# Sheet6.net
KiCad netlist of a schematic drawn in Altium Designer
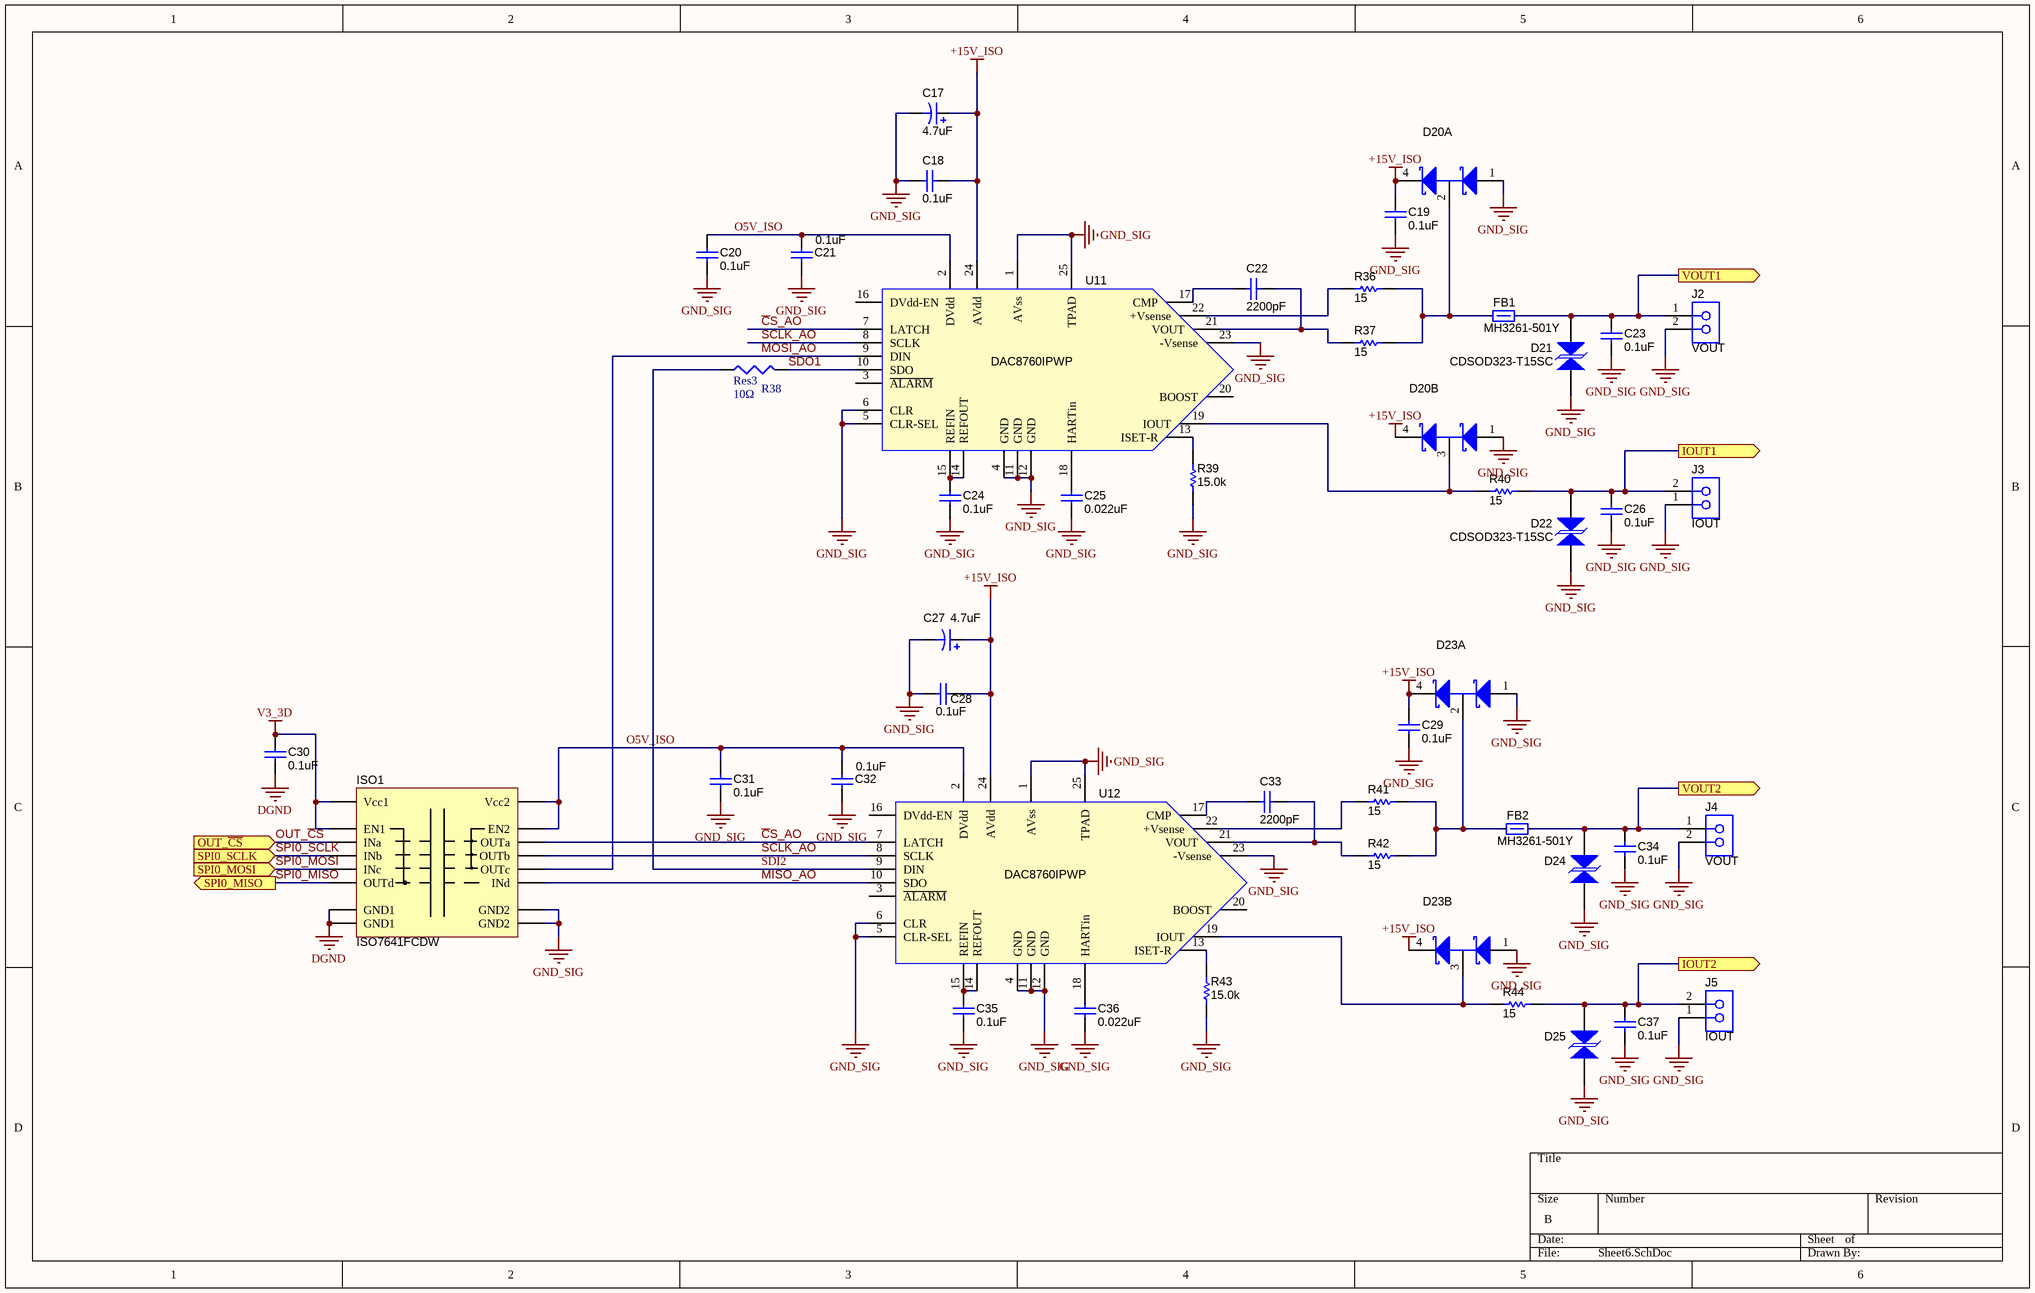
[diagram p0: Sheet6.SchDoc]

(export (version "E")
  (design (tool "Eeschema 10.0.6"))
  (components
    (comp (ref "C17")
      (value "293D475X9035C2TE3")
      (footprint "6032-28")
      (description "CAP, TA, 4.7uF, 35V, +/-10%, 1.9 ohm, SMD")
      (fields
        (field (name "VALUEDISPLAYED") "4.7uF")
        (field (name "MANUFACTURER") "Vishay-Sprague")
        (field (name "PUBLISHER") "Texas Instruments")
      )
      (libsource (lib "Capacitor_Tantalum") (part "293D475X9035C2TE3"))
    )
    (comp (ref "C18")
      (value "GRM188R71H104KA93D")
      (footprint "0805_cap")
      (description "CAP, CERM, 0.1uF, 50V, +/-10%, X7R, 0603")
      (fields
        (field (name "VALUEDISPLAYED") "0.1uF")
        (field (name "MANUFACTURER") "MuRata")
        (field (name "PUBLISHER") "Texas Instruments")
      )
      (libsource (lib "Capacitor_Ceramic") (part "GRM188R71H104KA93D"))
    )
    (comp (ref "C19")
      (value "GRM188R71H104KA93D")
      (footprint "0805_cap")
      (description "CAP, CERM, 0.1uF, 50V, +/-10%, X7R, 0603")
      (fields
        (field (name "VALUEDISPLAYED") "0.1uF")
        (field (name "MANUFACTURER") "MuRata")
        (field (name "PUBLISHER") "Texas Instruments")
      )
      (libsource (lib "Capacitor_Ceramic") (part "GRM188R71H104KA93D"))
    )
    (comp (ref "C20")
      (value "GRM188R71H104KA93D")
      (footprint "0805_cap")
      (description "CAP, CERM, 0.1uF, 50V, +/-10%, X7R, 0603")
      (fields
        (field (name "VALUEDISPLAYED") "0.1uF")
        (field (name "MANUFACTURER") "MuRata")
        (field (name "PUBLISHER") "Texas Instruments")
      )
      (libsource (lib "Capacitor_Ceramic") (part "GRM188R71H104KA93D"))
    )
    (comp (ref "C21")
      (value "GRM188R71H104KA93D")
      (footprint "0805_cap")
      (description "CAP, CERM, 0.1uF, 50V, +/-10%, X7R, 0603")
      (fields
        (field (name "VALUEDISPLAYED") "0.1uF")
        (field (name "MANUFACTURER") "MuRata")
        (field (name "PUBLISHER") "Texas Instruments")
      )
      (libsource (lib "Capacitor_Ceramic") (part "GRM188R71H104KA93D"))
    )
    (comp (ref "C22")
      (value "GRM1885C1H222JA01D")
      (footprint "0805_cap")
      (description "CAP, CERM, 2200pF, 50V, +/-5%, C0G/NP0, 0603")
      (fields
        (field (name "VALUEDISPLAYED") "2200pF")
        (field (name "MANUFACTURER") "MuRata")
        (field (name "PUBLISHER") "Texas Instruments")
      )
      (libsource (lib "Capacitor_Ceramic") (part "GRM1885C1H222JA01D"))
    )
    (comp (ref "C23")
      (value "06035C104KAT2A")
      (footprint "0805_cap")
      (description "CAP, CERM, 0.1uF, 50V, +/-10%, X7R, 0603")
      (fields
        (field (name "VALUEDISPLAYED") "0.1uF")
        (field (name "MANUFACTURER") "AVX")
        (field (name "PUBLISHER") "Texas Instruments")
      )
      (libsource (lib "Capacitor_Ceramic") (part "06035C104KAT2A"))
    )
    (comp (ref "C24")
      (value "06035C104KAT2A")
      (footprint "0805_cap")
      (description "CAP, CERM, 0.1uF, 50V, +/-10%, X7R, 0603")
      (fields
        (field (name "VALUEDISPLAYED") "0.1uF")
        (field (name "MANUFACTURER") "AVX")
        (field (name "PUBLISHER") "Texas Instruments")
      )
      (libsource (lib "Capacitor_Ceramic") (part "06035C104KAT2A"))
    )
    (comp (ref "C25")
      (value "C1608X7R1H223K")
      (footprint "0805_cap")
      (description "CAP, CERM, 0.022uF, 50V, +/-10%, X7R, 0603")
      (fields
        (field (name "VALUEDISPLAYED") "0.022uF")
        (field (name "MANUFACTURER") "TDK")
        (field (name "PUBLISHER") "Texas Instruments")
      )
      (libsource (lib "Capacitor_Ceramic") (part "C1608X7R1H223K"))
    )
    (comp (ref "C26")
      (value "06035C104KAT2A")
      (footprint "0805_cap")
      (description "CAP, CERM, 0.1uF, 50V, +/-10%, X7R, 0603")
      (fields
        (field (name "VALUEDISPLAYED") "0.1uF")
        (field (name "MANUFACTURER") "AVX")
        (field (name "PUBLISHER") "Texas Instruments")
      )
      (libsource (lib "Capacitor_Ceramic") (part "06035C104KAT2A"))
    )
    (comp (ref "C27")
      (value "293D475X9035C2TE3")
      (footprint "6032-28")
      (description "CAP, TA, 4.7uF, 35V, +/-10%, 1.9 ohm, SMD")
      (fields
        (field (name "VALUEDISPLAYED") "4.7uF")
        (field (name "MANUFACTURER") "Vishay-Sprague")
        (field (name "PUBLISHER") "Texas Instruments")
      )
      (libsource (lib "Capacitor_Tantalum") (part "293D475X9035C2TE3"))
    )
    (comp (ref "C28")
      (value "GRM188R71H104KA93D")
      (footprint "0805_cap")
      (description "CAP, CERM, 0.1uF, 50V, +/-10%, X7R, 0603")
      (fields
        (field (name "VALUEDISPLAYED") "0.1uF")
        (field (name "MANUFACTURER") "MuRata")
        (field (name "PUBLISHER") "Texas Instruments")
      )
      (libsource (lib "Capacitor_Ceramic") (part "GRM188R71H104KA93D"))
    )
    (comp (ref "C29")
      (value "GRM188R71H104KA93D")
      (footprint "0805_cap")
      (description "CAP, CERM, 0.1uF, 50V, +/-10%, X7R, 0603")
      (fields
        (field (name "VALUEDISPLAYED") "0.1uF")
        (field (name "MANUFACTURER") "MuRata")
        (field (name "PUBLISHER") "Texas Instruments")
      )
      (libsource (lib "Capacitor_Ceramic") (part "GRM188R71H104KA93D"))
    )
    (comp (ref "C30")
      (value "GRM188R71H104KA93D")
      (footprint "0805_cap")
      (description "CAP, CERM, 0.1uF, 50V, +/-10%, X7R, 0603")
      (fields
        (field (name "VALUEDISPLAYED") "0.1uF")
        (field (name "MANUFACTURER") "MuRata")
        (field (name "PUBLISHER") "Texas Instruments")
      )
      (libsource (lib "Capacitor_Ceramic") (part "GRM188R71H104KA93D"))
    )
    (comp (ref "C31")
      (value "GRM188R71H104KA93D")
      (footprint "0805_cap")
      (description "CAP, CERM, 0.1uF, 50V, +/-10%, X7R, 0603")
      (fields
        (field (name "VALUEDISPLAYED") "0.1uF")
        (field (name "MANUFACTURER") "MuRata")
        (field (name "PUBLISHER") "Texas Instruments")
      )
      (libsource (lib "Capacitor_Ceramic") (part "GRM188R71H104KA93D"))
    )
    (comp (ref "C32")
      (value "GRM188R71H104KA93D")
      (footprint "0805_cap")
      (description "CAP, CERM, 0.1uF, 50V, +/-10%, X7R, 0603")
      (fields
        (field (name "VALUEDISPLAYED") "0.1uF")
        (field (name "MANUFACTURER") "MuRata")
        (field (name "PUBLISHER") "Texas Instruments")
      )
      (libsource (lib "Capacitor_Ceramic") (part "GRM188R71H104KA93D"))
    )
    (comp (ref "C33")
      (value "GRM1885C1H222JA01D")
      (footprint "0805_cap")
      (description "CAP, CERM, 2200pF, 50V, +/-5%, C0G/NP0, 0603")
      (fields
        (field (name "VALUEDISPLAYED") "2200pF")
        (field (name "MANUFACTURER") "MuRata")
        (field (name "PUBLISHER") "Texas Instruments")
      )
      (libsource (lib "Capacitor_Ceramic") (part "GRM1885C1H222JA01D"))
    )
    (comp (ref "C34")
      (value "06035C104KAT2A")
      (footprint "0805_cap")
      (description "CAP, CERM, 0.1uF, 50V, +/-10%, X7R, 0603")
      (fields
        (field (name "VALUEDISPLAYED") "0.1uF")
        (field (name "MANUFACTURER") "AVX")
        (field (name "PUBLISHER") "Texas Instruments")
      )
      (libsource (lib "Capacitor_Ceramic") (part "06035C104KAT2A"))
    )
    (comp (ref "C35")
      (value "06035C104KAT2A")
      (footprint "0805_cap")
      (description "CAP, CERM, 0.1uF, 50V, +/-10%, X7R, 0603")
      (fields
        (field (name "VALUEDISPLAYED") "0.1uF")
        (field (name "MANUFACTURER") "AVX")
        (field (name "PUBLISHER") "Texas Instruments")
      )
      (libsource (lib "Capacitor_Ceramic") (part "06035C104KAT2A"))
    )
    (comp (ref "C36")
      (value "C1608X7R1H223K")
      (footprint "0805_cap")
      (description "CAP, CERM, 0.022uF, 50V, +/-10%, X7R, 0603")
      (fields
        (field (name "VALUEDISPLAYED") "0.022uF")
        (field (name "MANUFACTURER") "TDK")
        (field (name "PUBLISHER") "Texas Instruments")
      )
      (libsource (lib "Capacitor_Ceramic") (part "C1608X7R1H223K"))
    )
    (comp (ref "C37")
      (value "06035C104KAT2A")
      (footprint "0805_cap")
      (description "CAP, CERM, 0.1uF, 50V, +/-10%, X7R, 0603")
      (fields
        (field (name "VALUEDISPLAYED") "0.1uF")
        (field (name "MANUFACTURER") "AVX")
        (field (name "PUBLISHER") "Texas Instruments")
      )
      (libsource (lib "Capacitor_Ceramic") (part "06035C104KAT2A"))
    )
    (comp (ref "D20")
      (value "~")
      (footprint "SOT-143")
      (description "IC TVS ARRAY 2-LINE 70V SOT-143")
      (fields
        (field (name "MANUFACTURER") "Bourns")
        (field (name "PARTNUMBER") "CD143A-SR70")
        (field (name "SYMBOLCREATOR") "Use LDAP id")
      )
      (libsource (lib "DAC8760-Symbols") (part "CD143A-SR70"))
    )
    (comp (ref "D21")
      (value "CDSOD323-T15SC")
      (footprint "sod-323")
      (description "DIODE TVS ARRAY 15V SOD323")
      (fields (field (name "MANUFACTURER") "Bourns") (field (name "SYMBOLCREATOR") "Use LDAP id"))
      (libsource (lib "DAC8760-Symbols") (part "SMAJ15CA"))
    )
    (comp (ref "D22")
      (value "CDSOD323-T15SC")
      (footprint "sod-323")
      (description "DIODE TVS ARRAY 15V SOD323")
      (fields (field (name "MANUFACTURER") "Bourns") (field (name "SYMBOLCREATOR") "Use LDAP id"))
      (libsource (lib "DAC8760-Symbols") (part "SMAJ15CA"))
    )
    (comp (ref "D23")
      (value "~")
      (footprint "SOT-143")
      (description "IC TVS ARRAY 2-LINE 70V SOT-143")
      (fields
        (field (name "MANUFACTURER") "Bourns")
        (field (name "PARTNUMBER") "CD143A-SR70")
        (field (name "SYMBOLCREATOR") "Use LDAP id")
      )
      (libsource (lib "DAC8760-Symbols") (part "CD143A-SR70"))
    )
    (comp (ref "D24")
      (value "~")
      (footprint "sod-323")
      (description "DIODE TVS ARRAY 15V SOD323")
      (fields
        (field (name "MANUFACTURER") "Bourns")
        (field (name "PARTNUMBER") "CDSOD323-T15SC")
        (field (name "SYMBOLCREATOR") "Use LDAP id")
      )
      (libsource (lib "DAC8760-Symbols") (part "SMAJ15CA"))
    )
    (comp (ref "D25")
      (value "~")
      (footprint "sod-323")
      (description "DIODE TVS ARRAY 15V SOD323")
      (fields
        (field (name "MANUFACTURER") "Bourns")
        (field (name "PARTNUMBER") "CDSOD323-T15SC")
        (field (name "SYMBOLCREATOR") "Use LDAP id")
      )
      (libsource (lib "DAC8760-Symbols") (part "SMAJ15CA"))
    )
    (comp (ref "FB1")
      (value "MH3261-501Y")
      (footprint "1210")
      (description "BEAD FERRITE 500 OHM 3.0A 3216")
      (fields (field (name "MANUFACTURER") "Bourns Inc.") (field (name "PUBLISHER") "Texas Instruments"))
      (libsource (lib "MiscParts") (part "Ferrite_Bead"))
    )
    (comp (ref "FB2")
      (value "MH3261-501Y")
      (footprint "1210")
      (description "BEAD FERRITE 500 OHM 3.0A 3216")
      (fields (field (name "MANUFACTURER") "Bourns Inc.") (field (name "PUBLISHER") "Texas Instruments"))
      (libsource (lib "MiscParts") (part "Ferrite_Bead"))
    )
    (comp (ref "ISO1")
      (value "ISO7641FCDW")
      (footprint "M16B_N")
      (description "ISOLATOR DGTL 25MBPS 4CH 16SOIC")
      (fields
        (field (name "MANUFACTURER") "Texas Instruments Inc")
        (field (name "SYMBOLCREATOR") "Use LDAP id")
      )
      (libsource (lib "DAC8760-Symbols") (part "ISO7241"))
    )
    (comp (ref "J2")
      (value "VOUT")
      (footprint "ED555/2DS")
      (description "TERMINAL BLOCK 3.5MM 2POS PCB")
      (fields
        (field (name "PARTNUMBER") "ED555/2DS")
        (field (name "MANUFACTURER") "On Shore Technology Inc")
        (field (name "PUBLISHER") "Texas Instruments")
      )
      (libsource (lib "Connectors") (part "1727010"))
    )
    (comp (ref "J3")
      (value "IOUT")
      (footprint "ED555/2DS")
      (description "TERMINAL BLOCK 3.5MM 2POS PCB")
      (fields
        (field (name "PARTNUMBER") "ED555/2DS")
        (field (name "MANUFACTURER") "On Shore Technology Inc")
        (field (name "PUBLISHER") "Texas Instruments")
      )
      (libsource (lib "") (part "1727010_1"))
    )
    (comp (ref "J4")
      (value "VOUT")
      (footprint "ED555/2DS")
      (description "TERMINAL BLOCK 3.5MM 2POS PCB")
      (fields
        (field (name "PARTNUMBER") "ED555/2DS")
        (field (name "MANUFACTURER") "On Shore Technology Inc")
        (field (name "PUBLISHER") "Texas Instruments")
      )
      (libsource (lib "Connectors") (part "1727010"))
    )
    (comp (ref "J5")
      (value "IOUT")
      (footprint "ED555/2DS")
      (description "TERMINAL BLOCK 3.5MM 2POS PCB")
      (fields
        (field (name "PARTNUMBER") "ED555/2DS")
        (field (name "MANUFACTURER") "On Shore Technology Inc")
        (field (name "PUBLISHER") "Texas Instruments")
      )
      (libsource (lib "") (part "1727010_1"))
    )
    (comp (ref "R36")
      (value "15")
      (footprint "0805")
      (description "RES, 15 ohm, 5%, 0.1W, 0603")
      (fields
        (field (name "PARTNUMBER") "CRCW060315R0JNEA")
        (field (name "MANUFACTURER") "Vishay-Dale")
        (field (name "PUBLISHER") "Texas Instruments")
      )
      (libsource (lib "Resistor_0603") (part "CRCW060315R0JNEA"))
    )
    (comp (ref "R37")
      (value "15")
      (footprint "0805")
      (description "RES, 15 ohm, 5%, 0.1W, 0603")
      (fields
        (field (name "PARTNUMBER") "CRCW060315R0JNEA")
        (field (name "MANUFACTURER") "Vishay-Dale")
        (field (name "PUBLISHER") "Texas Instruments")
      )
      (libsource (lib "Resistor_0603") (part "CRCW060315R0JNEA"))
    )
    (comp (ref "R38")
      (value "Res3")
      (footprint "0805")
      (description "Resistor")
      (fields (field (name "ALTIUM_VALUE") "10Ω") (field (name "PUBLISHER") "Altium Limited"))
      (libsource (lib "Miscellaneous Devices") (part "Res3"))
    )
    (comp (ref "R39")
      (value "15.0k")
      (footprint "0805")
      (description "RES, 15.0k ohm, 0.1%, 0.1W, 0603")
      (fields
        (field (name "PARTNUMBER") "RT0603BRD0715KL")
        (field (name "MANUFACTURER") "Yageo America")
        (field (name "PUBLISHER") "Texas Instruments")
      )
      (libsource (lib "Resistor_0603") (part "RT0603BRD0715KL"))
    )
    (comp (ref "R40")
      (value "15")
      (footprint "1210")
      (description "RES 15 OHM 1W 5% 2512")
      (fields
        (field (name "PARTNUMBER") "RPC2512JT15R0")
        (field (name "MANUFACTURER") "Stackpole Electronics")
      )
      (libsource (lib "Resistor_OtherSMT") (part "CRA2512-FZ-R080ELF"))
    )
    (comp (ref "R41")
      (value "15")
      (footprint "0805")
      (description "RES, 15 ohm, 5%, 0.1W, 0603")
      (fields
        (field (name "PARTNUMBER") "CRCW060315R0JNEA")
        (field (name "MANUFACTURER") "Vishay-Dale")
        (field (name "PUBLISHER") "Texas Instruments")
      )
      (libsource (lib "Resistor_0603") (part "CRCW060315R0JNEA"))
    )
    (comp (ref "R42")
      (value "15")
      (footprint "0805")
      (description "RES, 15 ohm, 5%, 0.1W, 0603")
      (fields
        (field (name "PARTNUMBER") "CRCW060315R0JNEA")
        (field (name "MANUFACTURER") "Vishay-Dale")
        (field (name "PUBLISHER") "Texas Instruments")
      )
      (libsource (lib "Resistor_0603") (part "CRCW060315R0JNEA"))
    )
    (comp (ref "R43")
      (value "15.0k")
      (footprint "0805")
      (description "RES, 15.0k ohm, 0.1%, 0.1W, 0603")
      (fields
        (field (name "PARTNUMBER") "RT0603BRD0715KL")
        (field (name "MANUFACTURER") "Yageo America")
        (field (name "PUBLISHER") "Texas Instruments")
      )
      (libsource (lib "Resistor_0603") (part "RT0603BRD0715KL"))
    )
    (comp (ref "R44")
      (value "15")
      (footprint "1210")
      (description "RES 15 OHM 1W 5% 2512")
      (fields
        (field (name "PARTNUMBER") "RPC2512JT15R0")
        (field (name "MANUFACTURER") "Stackpole Electronics")
      )
      (libsource (lib "Resistor_OtherSMT") (part "CRA2512-FZ-R080ELF"))
    )
    (comp (ref "U11")
      (value "DAC8760IPWP")
      (footprint "PWP24-DIE84X166")
      (description "1-Channel, 16-Bit, Programmable Current/Voltage Output DAC for 4-20mA Current Loop Applications")
      (fields
        (field (name "MANUFACTURER") "Texas Instruments")
        (field (name "SYMBOLCREATOR") "x0120606")
        (field (name "PUBLISHER") "Texas Instruments")
      )
      (libsource (lib "dolphi_ecs") (part "DAC8760IPWP_1"))
    )
    (comp (ref "U12")
      (value "DAC8760IPWP")
      (footprint "PWP24-DIE84X166")
      (description "1-Channel, 16-Bit, Programmable Current/Voltage Output DAC for 4-20mA Current Loop Applications")
      (fields
        (field (name "MANUFACTURER") "Texas Instruments")
        (field (name "SYMBOLCREATOR") "x0120606")
        (field (name "PUBLISHER") "Texas Instruments")
      )
      (libsource (lib "dolphi_ecs") (part "DAC8760IPWP_1"))
    )
  )
  (nets
    (net (code "1") (name "+15V_ISO") (class "Default")
      (node (ref "C17") (pin "1") (pinfunction "+_1") (pintype "passive"))
      (node (ref "C18") (pin "1") (pinfunction "1_1") (pintype "passive"))
      (node (ref "C19") (pin "1") (pinfunction "1_1") (pintype "passive"))
      (node (ref "C27") (pin "1") (pinfunction "+_1") (pintype "passive"))
      (node (ref "C28") (pin "1") (pinfunction "1_1") (pintype "passive"))
      (node (ref "C29") (pin "1") (pinfunction "1_1") (pintype "passive"))
      (node (ref "D20") (pin "4") (pinfunction "4_4") (pintype "passive"))
      (node (ref "D23") (pin "4") (pinfunction "4_4") (pintype "passive"))
      (node (ref "U11") (pin "24") (pinfunction "AVdd_24") (pintype "passive"))
      (node (ref "U12") (pin "24") (pinfunction "AVdd_24") (pintype "passive"))
    )
    (net (code "2") (name "/IOUT1") (class "Default")
      (node (ref "C26") (pin "1") (pinfunction "1_1") (pintype "passive"))
      (node (ref "D22") (pin "1") (pinfunction "1_1") (pintype "passive"))
      (node (ref "J3") (pin "2") (pinfunction "2_2") (pintype "passive"))
      (node (ref "R40") (pin "2") (pinfunction "2_2") (pintype "passive"))
    )
    (net (code "3") (name "/IOUT2") (class "Default")
      (node (ref "C37") (pin "1") (pinfunction "1_1") (pintype "passive"))
      (node (ref "D25") (pin "1") (pinfunction "1_1") (pintype "passive"))
      (node (ref "J5") (pin "2") (pinfunction "2_2") (pintype "passive"))
      (node (ref "R44") (pin "2") (pinfunction "2_2") (pintype "passive"))
    )
    (net (code "4") (name "/MISO_AO") (class "Default")
      (node (ref "ISO1") (pin "11") (pinfunction "INd_11") (pintype "passive"))
      (node (ref "U12") (pin "10") (pinfunction "SDO_10") (pintype "passive"))
    )
    (net (code "5") (name "/MOSI_AO") (class "Default")
      (node (ref "ISO1") (pin "12") (pinfunction "OUTc_12") (pintype "passive"))
      (node (ref "U11") (pin "9") (pinfunction "DIN_9") (pintype "passive"))
    )
    (net (code "6") (name "/O5V_ISO") (class "Default")
      (node (ref "C20") (pin "1") (pinfunction "1_1") (pintype "passive"))
      (node (ref "C21") (pin "1") (pinfunction "1_1") (pintype "passive"))
      (node (ref "C31") (pin "1") (pinfunction "1_1") (pintype "passive"))
      (node (ref "C32") (pin "1") (pinfunction "1_1") (pintype "passive"))
      (node (ref "ISO1") (pin "10") (pinfunction "EN2_10") (pintype "passive"))
      (node (ref "ISO1") (pin "16") (pinfunction "Vcc2_16") (pintype "passive"))
      (node (ref "U11") (pin "2") (pinfunction "DVdd_2") (pintype "passive"))
      (node (ref "U12") (pin "2") (pinfunction "DVdd_2") (pintype "passive"))
    )
    (net (code "7") (name "/OUT_~{CS}") (class "Default")
      (node (ref "ISO1") (pin "3") (pinfunction "INa_3") (pintype "passive"))
    )
    (net (code "8") (name "/SCLK_AO") (class "Default")
      (node (ref "ISO1") (pin "13") (pinfunction "OUTb_13") (pintype "passive"))
      (node (ref "U11") (pin "8") (pinfunction "SCLK_8") (pintype "passive"))
      (node (ref "U12") (pin "8") (pinfunction "SCLK_8") (pintype "passive"))
    )
    (net (code "9") (name "/SDI2") (class "Default")
      (node (ref "R38") (pin "1") (pinfunction "1_1") (pintype "passive"))
      (node (ref "U12") (pin "9") (pinfunction "DIN_9") (pintype "passive"))
    )
    (net (code "10") (name "/SDO1") (class "Default")
      (node (ref "R38") (pin "2") (pinfunction "2_2") (pintype "passive"))
      (node (ref "U11") (pin "10") (pinfunction "SDO_10") (pintype "passive"))
    )
    (net (code "11") (name "/SPI0_MISO") (class "Default")
      (node (ref "ISO1") (pin "6") (pinfunction "OUTd_6") (pintype "passive"))
    )
    (net (code "12") (name "/SPI0_MOSI") (class "Default")
      (node (ref "ISO1") (pin "5") (pinfunction "INc_5") (pintype "passive"))
    )
    (net (code "13") (name "/SPI0_SCLK") (class "Default")
      (node (ref "ISO1") (pin "4") (pinfunction "INb_4") (pintype "passive"))
    )
    (net (code "14") (name "/VOUT1") (class "Default")
      (node (ref "C23") (pin "1") (pinfunction "1_1") (pintype "passive"))
      (node (ref "D21") (pin "1") (pinfunction "1_1") (pintype "passive"))
      (node (ref "FB1") (pin "2") (pinfunction "2_2") (pintype "passive"))
      (node (ref "J2") (pin "1") (pinfunction "1_1") (pintype "passive"))
    )
    (net (code "15") (name "/VOUT2") (class "Default")
      (node (ref "C34") (pin "1") (pinfunction "1_1") (pintype "passive"))
      (node (ref "D24") (pin "1") (pinfunction "1_1") (pintype "passive"))
      (node (ref "FB2") (pin "2") (pinfunction "2_2") (pintype "passive"))
      (node (ref "J4") (pin "1") (pinfunction "1_1") (pintype "passive"))
    )
    (net (code "16") (name "/~{C}S_AO") (class "Default")
      (node (ref "ISO1") (pin "14") (pinfunction "OUTa_14") (pintype "passive"))
      (node (ref "U11") (pin "7") (pinfunction "LATCH_7") (pintype "passive"))
      (node (ref "U12") (pin "7") (pinfunction "LATCH_7") (pintype "passive"))
    )
    (net (code "17") (name "DGND") (class "Default")
      (node (ref "C30") (pin "2") (pinfunction "2_2") (pintype "passive"))
      (node (ref "ISO1") (pin "2") (pinfunction "GND1_2") (pintype "passive"))
      (node (ref "ISO1") (pin "8") (pinfunction "GND1_8") (pintype "passive"))
    )
    (net (code "18") (name "GND_SIG") (class "Default")
      (node (ref "C17") (pin "2") (pinfunction "-_2") (pintype "passive"))
      (node (ref "C18") (pin "2") (pinfunction "2_2") (pintype "passive"))
      (node (ref "C19") (pin "2") (pinfunction "2_2") (pintype "passive"))
      (node (ref "C20") (pin "2") (pinfunction "2_2") (pintype "passive"))
      (node (ref "C21") (pin "2") (pinfunction "2_2") (pintype "passive"))
      (node (ref "C23") (pin "2") (pinfunction "2_2") (pintype "passive"))
      (node (ref "C24") (pin "2") (pinfunction "2_2") (pintype "passive"))
      (node (ref "C25") (pin "2") (pinfunction "2_2") (pintype "passive"))
      (node (ref "C26") (pin "2") (pinfunction "2_2") (pintype "passive"))
      (node (ref "C27") (pin "2") (pinfunction "-_2") (pintype "passive"))
      (node (ref "C28") (pin "2") (pinfunction "2_2") (pintype "passive"))
      (node (ref "C29") (pin "2") (pinfunction "2_2") (pintype "passive"))
      (node (ref "C31") (pin "2") (pinfunction "2_2") (pintype "passive"))
      (node (ref "C32") (pin "2") (pinfunction "2_2") (pintype "passive"))
      (node (ref "C34") (pin "2") (pinfunction "2_2") (pintype "passive"))
      (node (ref "C35") (pin "2") (pinfunction "2_2") (pintype "passive"))
      (node (ref "C36") (pin "2") (pinfunction "2_2") (pintype "passive"))
      (node (ref "C37") (pin "2") (pinfunction "2_2") (pintype "passive"))
      (node (ref "D20") (pin "1") (pinfunction "1_1") (pintype "passive"))
      (node (ref "D21") (pin "2") (pinfunction "2_2") (pintype "passive"))
      (node (ref "D22") (pin "2") (pinfunction "2_2") (pintype "passive"))
      (node (ref "D23") (pin "1") (pinfunction "1_1") (pintype "passive"))
      (node (ref "D24") (pin "2") (pinfunction "2_2") (pintype "passive"))
      (node (ref "D25") (pin "2") (pinfunction "2_2") (pintype "passive"))
      (node (ref "ISO1") (pin "15") (pinfunction "GND2_15") (pintype "passive"))
      (node (ref "ISO1") (pin "9") (pinfunction "GND2_9") (pintype "passive"))
      (node (ref "J2") (pin "2") (pinfunction "2_2") (pintype "passive"))
      (node (ref "J3") (pin "1") (pinfunction "1_1") (pintype "passive"))
      (node (ref "J4") (pin "2") (pinfunction "2_2") (pintype "passive"))
      (node (ref "J5") (pin "1") (pinfunction "1_1") (pintype "passive"))
      (node (ref "R39") (pin "1") (pinfunction "1_1") (pintype "passive"))
      (node (ref "R43") (pin "1") (pinfunction "1_1") (pintype "passive"))
      (node (ref "U11") (pin "1") (pinfunction "AVss_1") (pintype "passive"))
      (node (ref "U11") (pin "11") (pinfunction "GND_11") (pintype "passive"))
      (node (ref "U11") (pin "12") (pinfunction "GND_12") (pintype "passive"))
      (node (ref "U11") (pin "23") (pinfunction "-Vsense_23") (pintype "passive"))
      (node (ref "U11") (pin "25") (pinfunction "TPAD_25") (pintype "passive"))
      (node (ref "U11") (pin "4") (pinfunction "GND_4") (pintype "passive"))
      (node (ref "U11") (pin "5") (pinfunction "CLR-SEL_5") (pintype "passive"))
      (node (ref "U11") (pin "6") (pinfunction "CLR_6") (pintype "passive"))
      (node (ref "U12") (pin "1") (pinfunction "AVss_1") (pintype "passive"))
      (node (ref "U12") (pin "11") (pinfunction "GND_11") (pintype "passive"))
      (node (ref "U12") (pin "12") (pinfunction "GND_12") (pintype "passive"))
      (node (ref "U12") (pin "23") (pinfunction "-Vsense_23") (pintype "passive"))
      (node (ref "U12") (pin "25") (pinfunction "TPAD_25") (pintype "passive"))
      (node (ref "U12") (pin "4") (pinfunction "GND_4") (pintype "passive"))
      (node (ref "U12") (pin "5") (pinfunction "CLR-SEL_5") (pintype "passive"))
      (node (ref "U12") (pin "6") (pinfunction "CLR_6") (pintype "passive"))
    )
    (net (code "19") (name "Net-(D20-Pad2)") (class "Default")
      (node (ref "D20") (pin "2") (pinfunction "2_2") (pintype "passive"))
      (node (ref "FB1") (pin "1") (pinfunction "1_1") (pintype "passive"))
      (node (ref "R36") (pin "2") (pinfunction "2_2") (pintype "passive"))
      (node (ref "R37") (pin "2") (pinfunction "2_2") (pintype "passive"))
    )
    (net (code "20") (name "Net-(D23-Pad2)") (class "Default")
      (node (ref "D23") (pin "2") (pinfunction "2_2") (pintype "passive"))
      (node (ref "FB2") (pin "1") (pinfunction "1_1") (pintype "passive"))
      (node (ref "R41") (pin "2") (pinfunction "2_2") (pintype "passive"))
      (node (ref "R42") (pin "2") (pinfunction "2_2") (pintype "passive"))
    )
    (net (code "21") (name "Net-(U11-+Vsense)") (class "Default")
      (node (ref "R36") (pin "1") (pinfunction "1_1") (pintype "passive"))
      (node (ref "U11") (pin "22") (pinfunction "+Vsense_22") (pintype "passive"))
    )
    (net (code "22") (name "Net-(U11-CMP)") (class "Default")
      (node (ref "C22") (pin "2") (pinfunction "2_2") (pintype "passive"))
      (node (ref "U11") (pin "17") (pinfunction "CMP_17") (pintype "passive"))
    )
    (net (code "23") (name "Net-(U11-HARTin)") (class "Default")
      (node (ref "C25") (pin "1") (pinfunction "1_1") (pintype "passive"))
      (node (ref "U11") (pin "18") (pinfunction "HARTin_18") (pintype "passive"))
    )
    (net (code "24") (name "Net-(U11-IOUT)") (class "Default")
      (node (ref "D20") (pin "3") (pinfunction "3_3") (pintype "passive"))
      (node (ref "R40") (pin "1") (pinfunction "1_1") (pintype "passive"))
      (node (ref "U11") (pin "19") (pinfunction "IOUT_19") (pintype "passive"))
    )
    (net (code "25") (name "Net-(U11-ISET-R)") (class "Default")
      (node (ref "R39") (pin "2") (pinfunction "2_2") (pintype "passive"))
      (node (ref "U11") (pin "13") (pinfunction "ISET-R_13") (pintype "passive"))
    )
    (net (code "26") (name "Net-(U11-REFIN)") (class "Default")
      (node (ref "C24") (pin "1") (pinfunction "1_1") (pintype "passive"))
      (node (ref "U11") (pin "14") (pinfunction "REFOUT_14") (pintype "passive"))
      (node (ref "U11") (pin "15") (pinfunction "REFIN_15") (pintype "passive"))
    )
    (net (code "27") (name "Net-(U11-VOUT)") (class "Default")
      (node (ref "C22") (pin "1") (pinfunction "1_1") (pintype "passive"))
      (node (ref "R37") (pin "1") (pinfunction "1_1") (pintype "passive"))
      (node (ref "U11") (pin "21") (pinfunction "VOUT_21") (pintype "passive"))
    )
    (net (code "28") (name "Net-(U12-+Vsense)") (class "Default")
      (node (ref "R41") (pin "1") (pinfunction "1_1") (pintype "passive"))
      (node (ref "U12") (pin "22") (pinfunction "+Vsense_22") (pintype "passive"))
    )
    (net (code "29") (name "Net-(U12-CMP)") (class "Default")
      (node (ref "C33") (pin "2") (pinfunction "2_2") (pintype "passive"))
      (node (ref "U12") (pin "17") (pinfunction "CMP_17") (pintype "passive"))
    )
    (net (code "30") (name "Net-(U12-HARTin)") (class "Default")
      (node (ref "C36") (pin "1") (pinfunction "1_1") (pintype "passive"))
      (node (ref "U12") (pin "18") (pinfunction "HARTin_18") (pintype "passive"))
    )
    (net (code "31") (name "Net-(U12-IOUT)") (class "Default")
      (node (ref "D23") (pin "3") (pinfunction "3_3") (pintype "passive"))
      (node (ref "R44") (pin "1") (pinfunction "1_1") (pintype "passive"))
      (node (ref "U12") (pin "19") (pinfunction "IOUT_19") (pintype "passive"))
    )
    (net (code "32") (name "Net-(U12-ISET-R)") (class "Default")
      (node (ref "R43") (pin "2") (pinfunction "2_2") (pintype "passive"))
      (node (ref "U12") (pin "13") (pinfunction "ISET-R_13") (pintype "passive"))
    )
    (net (code "33") (name "Net-(U12-REFIN)") (class "Default")
      (node (ref "C35") (pin "1") (pinfunction "1_1") (pintype "passive"))
      (node (ref "U12") (pin "14") (pinfunction "REFOUT_14") (pintype "passive"))
      (node (ref "U12") (pin "15") (pinfunction "REFIN_15") (pintype "passive"))
    )
    (net (code "34") (name "Net-(U12-VOUT)") (class "Default")
      (node (ref "C33") (pin "1") (pinfunction "1_1") (pintype "passive"))
      (node (ref "R42") (pin "1") (pinfunction "1_1") (pintype "passive"))
      (node (ref "U12") (pin "21") (pinfunction "VOUT_21") (pintype "passive"))
    )
    (net (code "35") (name "V3_3D") (class "Default")
      (node (ref "C30") (pin "1") (pinfunction "1_1") (pintype "passive"))
      (node (ref "ISO1") (pin "1") (pinfunction "Vcc1_1") (pintype "passive"))
      (node (ref "ISO1") (pin "7") (pinfunction "EN1_7") (pintype "passive"))
    )
    (net (code "36") (name "unconnected-(U11-BOOST-Pad20)") (class "Default")
      (node (ref "U11") (pin "20") (pinfunction "BOOST_20") (pintype "passive"))
    )
    (net (code "37") (name "unconnected-(U11-DVdd-EN-Pad16)") (class "Default")
      (node (ref "U11") (pin "16") (pinfunction "DVdd-EN_16") (pintype "passive"))
    )
    (net (code "38") (name "unconnected-(U11-~{ALARM}-Pad3)") (class "Default")
      (node (ref "U11") (pin "3") (pinfunction "~{ALARM}_3") (pintype "passive"))
    )
    (net (code "39") (name "unconnected-(U12-BOOST-Pad20)") (class "Default")
      (node (ref "U12") (pin "20") (pinfunction "BOOST_20") (pintype "passive"))
    )
    (net (code "40") (name "unconnected-(U12-DVdd-EN-Pad16)") (class "Default")
      (node (ref "U12") (pin "16") (pinfunction "DVdd-EN_16") (pintype "passive"))
    )
    (net (code "41") (name "unconnected-(U12-~{ALARM}-Pad3)") (class "Default")
      (node (ref "U12") (pin "3") (pinfunction "~{ALARM}_3") (pintype "passive"))
    )
  )
)
